# Qwiic_Twist.net
KiCad netlist of a schematic drawn in EAGLE
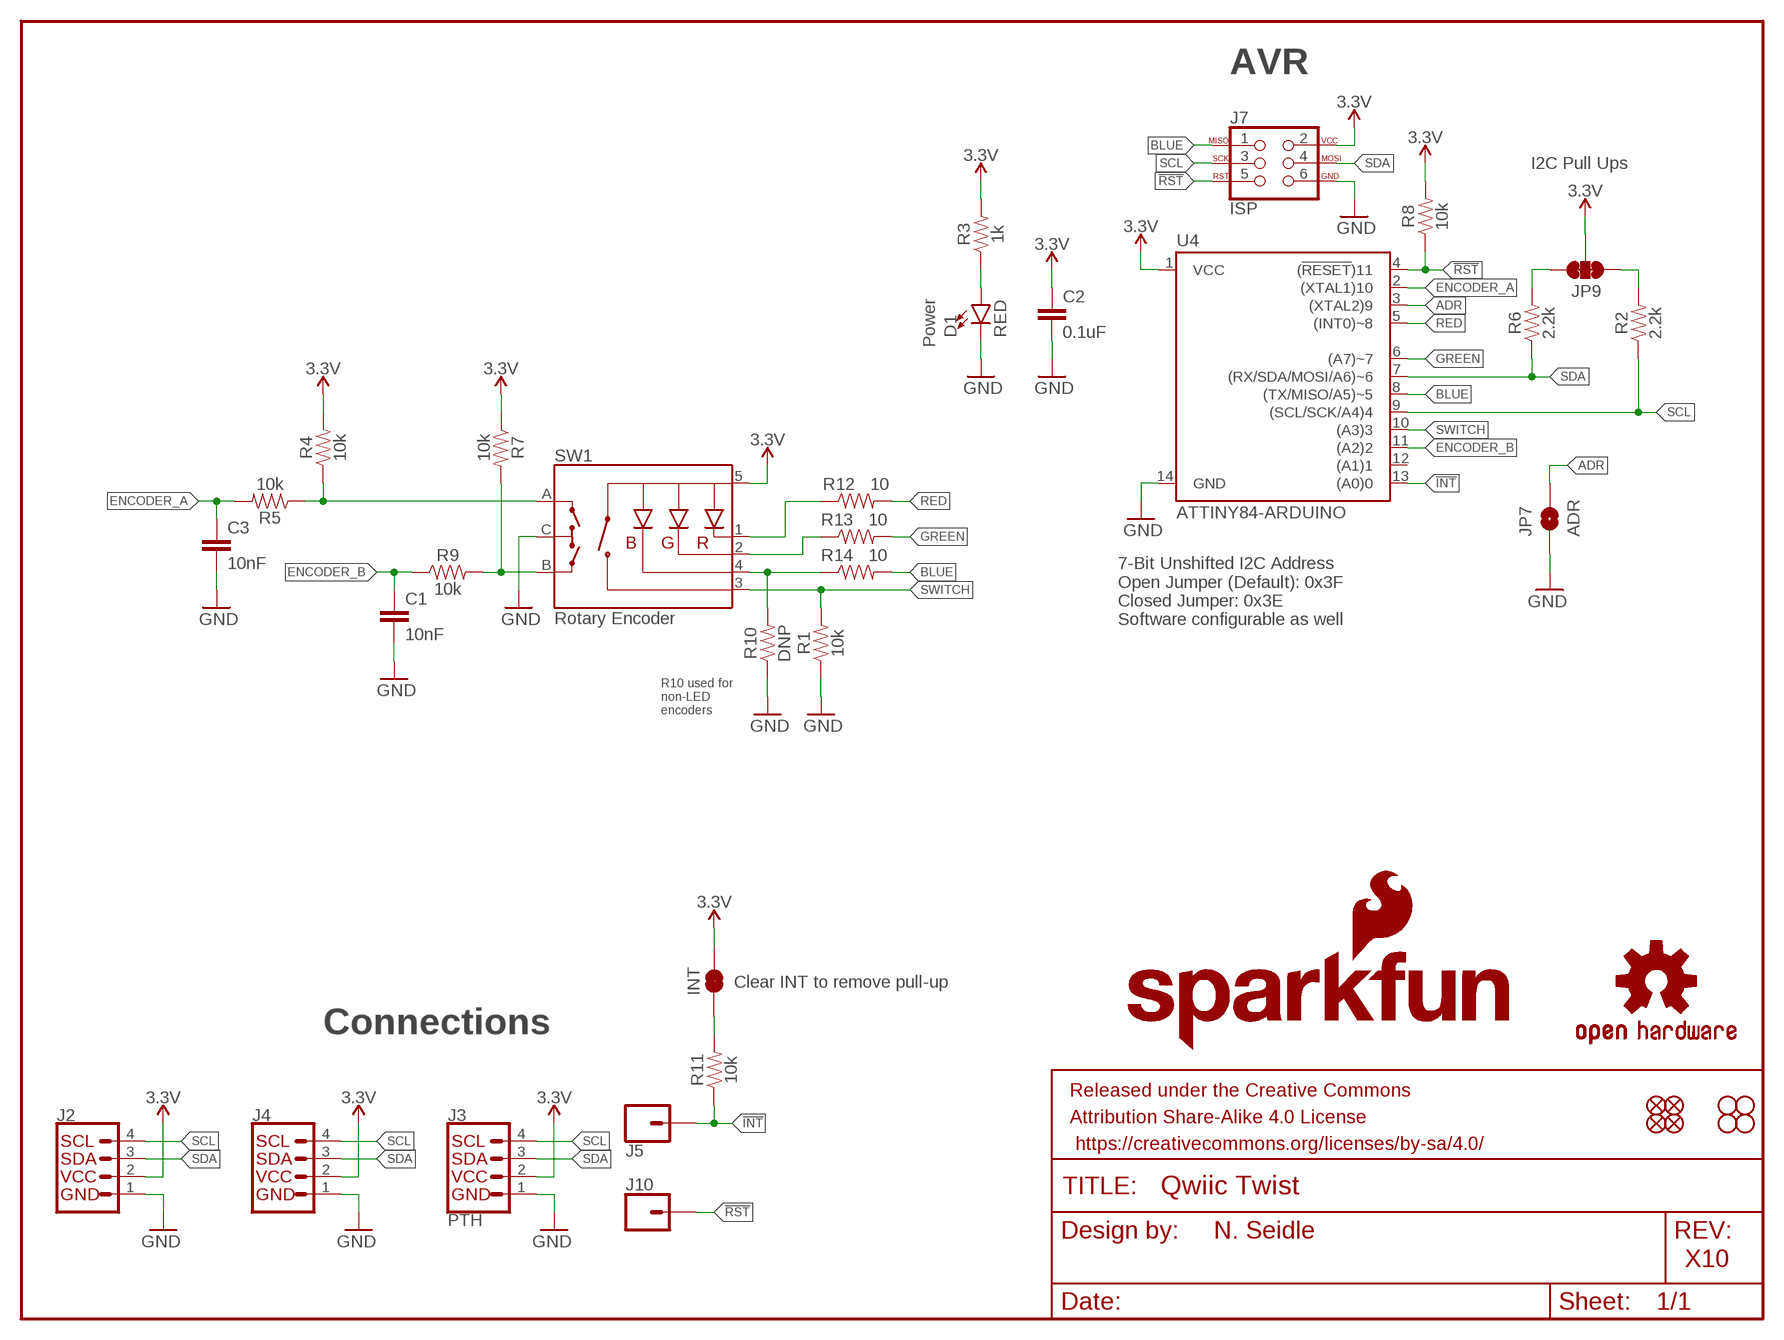
[diagram p0: schematic, sheet 1]

(export (version "E")
  (design (tool "Eeschema 10.0.6"))
  (components
    (comp (ref "C1")
      (value "10nF")
      (footprint "eagle-import:0603")
      (libsource (lib "eagle-import") (part "10NF-0603-50V-10%"))
    )
    (comp (ref "C2")
      (value "0.1uF")
      (footprint "eagle-import:0603")
      (libsource (lib "eagle-import") (part "0.1UF-0603-25V-(+80/-20%)"))
    )
    (comp (ref "C3")
      (value "10nF")
      (footprint "eagle-import:0603")
      (libsource (lib "eagle-import") (part "10NF-0603-50V-10%"))
    )
    (comp (ref "D1")
      (value "RED")
      (footprint "eagle-import:LED-0603")
      (libsource (lib "eagle-import") (part "LED-RED0603"))
    )
    (comp (ref "FRAME1")
      (value "FRAME-LETTER")
      (footprint "eagle-import:CREATIVE_COMMONS")
      (libsource (lib "eagle-import") (part "FRAME-LETTER"))
    )
    (comp (ref "INT")
      (value "JUMPER-SMT_2_NC_TRACE_SILK")
      (footprint "eagle-import:SMT-JUMPER_2_NC_TRACE_SILK")
      (libsource (lib "eagle-import") (part "JUMPER-SMT_2_NC_TRACE_SILK"))
    )
    (comp (ref "J2")
      (value "QWIIC_CONNECTORJS-1MM")
      (footprint "eagle-import:1X04_1MM_RA")
      (libsource (lib "eagle-import") (part "QWIIC_CONNECTORJS-1MM"))
    )
    (comp (ref "J3")
      (value "PTH")
      (footprint "eagle-import:1X04_NO_SILK")
      (libsource (lib "eagle-import") (part "I2C_STANDARD_NO_SILK"))
    )
    (comp (ref "J4")
      (value "QWIIC_CONNECTORJS-1MM")
      (footprint "eagle-import:1X04_1MM_RA")
      (libsource (lib "eagle-import") (part "QWIIC_CONNECTORJS-1MM"))
    )
    (comp (ref "J5")
      (value "CONN_01PTH_NO_SILK_YES_STOP")
      (footprint "eagle-import:1X01_NO_SILK")
      (libsource (lib "eagle-import") (part "CONN_01PTH_NO_SILK_YES_STOP"))
    )
    (comp (ref "J7")
      (value "ISP")
      (footprint "eagle-import:2X3_TEST_POINTS")
      (libsource (lib "eagle-import") (part "AVR_SPI_PROG_3X2TESTPOINTS"))
    )
    (comp (ref "J10")
      (value "CONN_01PTH_NO_SILK_YES_STOP")
      (footprint "eagle-import:1X01_NO_SILK")
      (libsource (lib "eagle-import") (part "CONN_01PTH_NO_SILK_YES_STOP"))
    )
    (comp (ref "JP1")
      (value "FIDUCIALUFIDUCIAL")
      (footprint "eagle-import:MICRO-FIDUCIAL")
      (libsource (lib "eagle-import") (part "FIDUCIALUFIDUCIAL"))
    )
    (comp (ref "JP2")
      (value "FIDUCIALUFIDUCIAL")
      (footprint "eagle-import:MICRO-FIDUCIAL")
      (libsource (lib "eagle-import") (part "FIDUCIALUFIDUCIAL"))
    )
    (comp (ref "JP3")
      (value "STAND-OFF")
      (footprint "eagle-import:STAND-OFF")
      (libsource (lib "eagle-import") (part "STAND-OFF"))
    )
    (comp (ref "JP4")
      (value "STAND-OFF")
      (footprint "eagle-import:STAND-OFF")
      (libsource (lib "eagle-import") (part "STAND-OFF"))
    )
    (comp (ref "JP5")
      (value "FIDUCIALUFIDUCIAL")
      (footprint "eagle-import:MICRO-FIDUCIAL")
      (libsource (lib "eagle-import") (part "FIDUCIALUFIDUCIAL"))
    )
    (comp (ref "JP6")
      (value "FIDUCIALUFIDUCIAL")
      (footprint "eagle-import:MICRO-FIDUCIAL")
      (libsource (lib "eagle-import") (part "FIDUCIALUFIDUCIAL"))
    )
    (comp (ref "JP7")
      (value "ADR")
      (footprint "eagle-import:SMT-JUMPER_2_NO_SILK")
      (libsource (lib "eagle-import") (part "JUMPER-SMT_2_NO_SILK"))
    )
    (comp (ref "JP9")
      (value "JUMPER-SMT_3_2-NC_TRACE_SILK")
      (footprint "eagle-import:SMT-JUMPER_3_2-NC_TRACE_SILK")
      (libsource (lib "eagle-import") (part "JUMPER-SMT_3_2-NC_TRACE_SILK"))
    )
    (comp (ref "JP11")
      (value "STAND-OFF")
      (footprint "eagle-import:STAND-OFF")
      (libsource (lib "eagle-import") (part "STAND-OFF"))
    )
    (comp (ref "JP13")
      (value "STAND-OFF")
      (footprint "eagle-import:STAND-OFF")
      (libsource (lib "eagle-import") (part "STAND-OFF"))
    )
    (comp (ref "LOGO1")
      (value "OSHW-LOGOMINI")
      (footprint "eagle-import:OSHW-LOGO-MINI")
      (libsource (lib "eagle-import") (part "OSHW-LOGOMINI"))
    )
    (comp (ref "LOGO2")
      (value "SFE_LOGO_NAME_FLAME.1_INCH")
      (footprint "eagle-import:SFE_LOGO_NAME_FLAME_.1")
      (libsource (lib "eagle-import") (part "SFE_LOGO_NAME_FLAME.1_INCH"))
    )
    (comp (ref "LOGO3")
      (value "SFE_LOGO_FLAME.1EXP")
      (footprint "eagle-import:SFE_LOGO_FLAME_COPPER_EXPOSED_.1")
      (libsource (lib "eagle-import") (part "SFE_LOGO_FLAME.1EXP"))
    )
    (comp (ref "R1")
      (value "10k")
      (footprint "eagle-import:0603")
      (libsource (lib "eagle-import") (part "10KOHM-0603-1/10W-1%"))
    )
    (comp (ref "R2")
      (value "2.2k")
      (footprint "eagle-import:0603")
      (libsource (lib "eagle-import") (part "2.2KOHM-0603-1/10W-1%"))
    )
    (comp (ref "R3")
      (value "1k")
      (footprint "eagle-import:0603")
      (libsource (lib "eagle-import") (part "1KOHM-0603-1/10W-1%"))
    )
    (comp (ref "R4")
      (value "10k")
      (footprint "eagle-import:0603")
      (libsource (lib "eagle-import") (part "10KOHM-0603-1/10W-1%"))
    )
    (comp (ref "R5")
      (value "10k")
      (footprint "eagle-import:0603")
      (libsource (lib "eagle-import") (part "10KOHM-0603-1/10W-1%"))
    )
    (comp (ref "R6")
      (value "2.2k")
      (footprint "eagle-import:0603")
      (libsource (lib "eagle-import") (part "2.2KOHM-0603-1/10W-1%"))
    )
    (comp (ref "R7")
      (value "10k")
      (footprint "eagle-import:0603")
      (libsource (lib "eagle-import") (part "10KOHM-0603-1/10W-1%"))
    )
    (comp (ref "R8")
      (value "10k")
      (footprint "eagle-import:0603")
      (libsource (lib "eagle-import") (part "10KOHM-0603-1/10W-1%"))
    )
    (comp (ref "R9")
      (value "10k")
      (footprint "eagle-import:0603")
      (libsource (lib "eagle-import") (part "10KOHM-0603-1/10W-1%"))
    )
    (comp (ref "R10")
      (value "DNP")
      (footprint "eagle-import:0603")
      (libsource (lib "eagle-import") (part "10KOHM-0603-1/10W-1%"))
    )
    (comp (ref "R11")
      (value "10k")
      (footprint "eagle-import:0603")
      (libsource (lib "eagle-import") (part "10KOHM-0603-1/10W-1%"))
    )
    (comp (ref "R12")
      (value "10")
      (footprint "eagle-import:0603")
      (libsource (lib "eagle-import") (part "10OHM-0603-1/10W-1%"))
    )
    (comp (ref "R13")
      (value "10")
      (footprint "eagle-import:0603")
      (libsource (lib "eagle-import") (part "10OHM-0603-1/10W-1%"))
    )
    (comp (ref "R14")
      (value "10")
      (footprint "eagle-import:0603")
      (libsource (lib "eagle-import") (part "10OHM-0603-1/10W-1%"))
    )
    (comp (ref "SW1")
      (value "Rotary Encoder")
      (footprint "eagle-import:ENCODER_LED_3_KIT")
      (libsource (lib "eagle-import") (part "ENCODER-RGB-SWITCHKIT"))
    )
    (comp (ref "U4")
      (value "ATTINY84-ARDUINO")
      (footprint "eagle-import:SO14")
      (libsource (lib "eagle-import") (part "ATTINY84-ARDUINO"))
    )
  )
  (nets
    (net (code "1") (name "/~{INT}") (class "Default")
      (node (ref "J5") (pin "1") (pinfunction "1_1") (pintype "passive"))
      (node (ref "R11") (pin "1") (pinfunction "1_1") (pintype "passive"))
      (node (ref "U4") (pin "13") (pinfunction "(A0)0_13") (pintype "bidirectional"))
    )
    (net (code "2") (name "/~{RST}") (class "Default")
      (node (ref "J10") (pin "1") (pinfunction "1_1") (pintype "passive"))
      (node (ref "J7") (pin "5") (pinfunction "5_5") (pintype "passive"))
      (node (ref "R8") (pin "1") (pinfunction "1_1") (pintype "passive"))
      (node (ref "U4") (pin "4") (pinfunction "(~{RESET})11_4") (pintype "bidirectional"))
    )
    (net (code "3") (name "3.3V") (class "Default")
      (node (ref "C2") (pin "1") (pinfunction "1_1") (pintype "passive"))
      (node (ref "INT") (pin "2") (pinfunction "2_2") (pintype "passive"))
      (node (ref "J2") (pin "2") (pinfunction "2_2") (pintype "power_in"))
      (node (ref "J3") (pin "2") (pinfunction "VCC_2") (pintype "power_in"))
      (node (ref "J4") (pin "2") (pinfunction "2_2") (pintype "power_in"))
      (node (ref "J7") (pin "2") (pinfunction "2_2") (pintype "passive"))
      (node (ref "JP9") (pin "2") (pinfunction "2_2") (pintype "passive"))
      (node (ref "R3") (pin "2") (pinfunction "2_2") (pintype "passive"))
      (node (ref "R4") (pin "2") (pinfunction "2_2") (pintype "passive"))
      (node (ref "R7") (pin "1") (pinfunction "1_1") (pintype "passive"))
      (node (ref "R8") (pin "2") (pinfunction "2_2") (pintype "passive"))
      (node (ref "SW1") (pin "5") (pinfunction "+_5") (pintype "passive"))
      (node (ref "U4") (pin "1") (pinfunction "VCC_1") (pintype "bidirectional"))
    )
    (net (code "4") (name "ADR") (class "Default")
      (node (ref "JP7") (pin "2") (pinfunction "2_2") (pintype "passive"))
      (node (ref "U4") (pin "3") (pinfunction "(XTAL2)9_3") (pintype "bidirectional"))
    )
    (net (code "5") (name "BLUE") (class "Default")
      (node (ref "J7") (pin "1") (pinfunction "1_1") (pintype "passive"))
      (node (ref "R14") (pin "2") (pinfunction "2_2") (pintype "passive"))
      (node (ref "U4") (pin "8") (pinfunction "(TX/MISO/A5)~{5}_8") (pintype "bidirectional"))
    )
    (net (code "6") (name "ENCODER_A") (class "Default")
      (node (ref "C3") (pin "1") (pinfunction "1_1") (pintype "passive"))
      (node (ref "R5") (pin "2") (pinfunction "2_2") (pintype "passive"))
      (node (ref "U4") (pin "2") (pinfunction "(XTAL1)10_2") (pintype "bidirectional"))
    )
    (net (code "7") (name "ENCODER_B") (class "Default")
      (node (ref "C1") (pin "1") (pinfunction "1_1") (pintype "passive"))
      (node (ref "R9") (pin "1") (pinfunction "1_1") (pintype "passive"))
      (node (ref "U4") (pin "11") (pinfunction "(A2)2_11") (pintype "bidirectional"))
    )
    (net (code "8") (name "GND") (class "Default")
      (node (ref "C1") (pin "2") (pinfunction "2_2") (pintype "passive"))
      (node (ref "C2") (pin "2") (pinfunction "2_2") (pintype "passive"))
      (node (ref "C3") (pin "2") (pinfunction "2_2") (pintype "passive"))
      (node (ref "D1") (pin "C") (pinfunction "C_C") (pintype "passive"))
      (node (ref "J2") (pin "1") (pinfunction "1_1") (pintype "power_in"))
      (node (ref "J3") (pin "1") (pinfunction "GND_1") (pintype "power_in"))
      (node (ref "J4") (pin "1") (pinfunction "1_1") (pintype "power_in"))
      (node (ref "J7") (pin "6") (pinfunction "6_6") (pintype "passive"))
      (node (ref "JP7") (pin "1") (pinfunction "1_1") (pintype "passive"))
      (node (ref "R1") (pin "1") (pinfunction "1_1") (pintype "passive"))
      (node (ref "R10") (pin "1") (pinfunction "1_1") (pintype "passive"))
      (node (ref "SW1") (pin "C") (pinfunction "C_C") (pintype "bidirectional"))
      (node (ref "U4") (pin "14") (pinfunction "GND_14") (pintype "bidirectional"))
    )
    (net (code "9") (name "GREEN") (class "Default")
      (node (ref "R13") (pin "2") (pinfunction "2_2") (pintype "passive"))
      (node (ref "U4") (pin "6") (pinfunction "(A7)~{7}_6") (pintype "bidirectional"))
    )
    (net (code "10") (name "Net-(D1-PadA)") (class "Default")
      (node (ref "D1") (pin "A") (pinfunction "A_A") (pintype "passive"))
      (node (ref "R3") (pin "1") (pinfunction "1_1") (pintype "passive"))
    )
    (net (code "11") (name "Net-(INT-Pad1)") (class "Default")
      (node (ref "INT") (pin "1") (pinfunction "1_1") (pintype "passive"))
      (node (ref "R11") (pin "2") (pinfunction "2_2") (pintype "passive"))
    )
    (net (code "12") (name "Net-(JP9-Pad1)") (class "Default")
      (node (ref "JP9") (pin "1") (pinfunction "1_1") (pintype "passive"))
      (node (ref "R2") (pin "2") (pinfunction "2_2") (pintype "passive"))
    )
    (net (code "13") (name "Net-(JP9-Pad3)") (class "Default")
      (node (ref "JP9") (pin "3") (pinfunction "3_3") (pintype "passive"))
      (node (ref "R6") (pin "2") (pinfunction "2_2") (pintype "passive"))
    )
    (net (code "14") (name "Net-(R4-Pad1)") (class "Default")
      (node (ref "R4") (pin "1") (pinfunction "1_1") (pintype "passive"))
      (node (ref "R5") (pin "1") (pinfunction "1_1") (pintype "passive"))
      (node (ref "SW1") (pin "A") (pinfunction "A_A") (pintype "bidirectional"))
    )
    (net (code "15") (name "Net-(R7-Pad2)") (class "Default")
      (node (ref "R7") (pin "2") (pinfunction "2_2") (pintype "passive"))
      (node (ref "R9") (pin "2") (pinfunction "2_2") (pintype "passive"))
      (node (ref "SW1") (pin "B") (pinfunction "B_B") (pintype "bidirectional"))
    )
    (net (code "16") (name "Net-(SW1--B)") (class "Default")
      (node (ref "R10") (pin "2") (pinfunction "2_2") (pintype "passive"))
      (node (ref "R14") (pin "1") (pinfunction "1_1") (pintype "passive"))
      (node (ref "SW1") (pin "4") (pinfunction "-B_4") (pintype "passive"))
    )
    (net (code "17") (name "Net-(SW1--G)") (class "Default")
      (node (ref "R13") (pin "1") (pinfunction "1_1") (pintype "passive"))
      (node (ref "SW1") (pin "2") (pinfunction "-G_2") (pintype "passive"))
    )
    (net (code "18") (name "Net-(SW1--R)") (class "Default")
      (node (ref "R12") (pin "1") (pinfunction "1_1") (pintype "passive"))
      (node (ref "SW1") (pin "1") (pinfunction "-R_1") (pintype "passive"))
    )
    (net (code "19") (name "RED") (class "Default")
      (node (ref "R12") (pin "2") (pinfunction "2_2") (pintype "passive"))
      (node (ref "U4") (pin "5") (pinfunction "(INT0)~{8}_5") (pintype "bidirectional"))
    )
    (net (code "20") (name "SCL") (class "Default")
      (node (ref "J2") (pin "4") (pinfunction "4_4") (pintype "passive"))
      (node (ref "J3") (pin "4") (pinfunction "SCL_4") (pintype "passive"))
      (node (ref "J4") (pin "4") (pinfunction "4_4") (pintype "passive"))
      (node (ref "J7") (pin "3") (pinfunction "3_3") (pintype "passive"))
      (node (ref "R2") (pin "1") (pinfunction "1_1") (pintype "passive"))
      (node (ref "U4") (pin "9") (pinfunction "(SCL/SCK/A4)4_9") (pintype "bidirectional"))
    )
    (net (code "21") (name "SDA") (class "Default")
      (node (ref "J2") (pin "3") (pinfunction "3_3") (pintype "passive"))
      (node (ref "J3") (pin "3") (pinfunction "SDA_3") (pintype "passive"))
      (node (ref "J4") (pin "3") (pinfunction "3_3") (pintype "passive"))
      (node (ref "J7") (pin "4") (pinfunction "4_4") (pintype "passive"))
      (node (ref "R6") (pin "1") (pinfunction "1_1") (pintype "passive"))
      (node (ref "U4") (pin "7") (pinfunction "(RX/SDA/MOSI/A6)~{6}_7") (pintype "bidirectional"))
    )
    (net (code "22") (name "SWITCH") (class "Default")
      (node (ref "R1") (pin "2") (pinfunction "2_2") (pintype "passive"))
      (node (ref "SW1") (pin "3") (pinfunction "SW_3") (pintype "passive"))
      (node (ref "U4") (pin "10") (pinfunction "(A3)3_10") (pintype "bidirectional"))
    )
    (net (code "23") (name "unconnected-(U4-(A1)1-Pad12)") (class "Default")
      (node (ref "U4") (pin "12") (pinfunction "(A1)1_12") (pintype "bidirectional"))
    )
  )
)
